# Pinout.net
KiCad netlist of a schematic drawn in Altium Designer
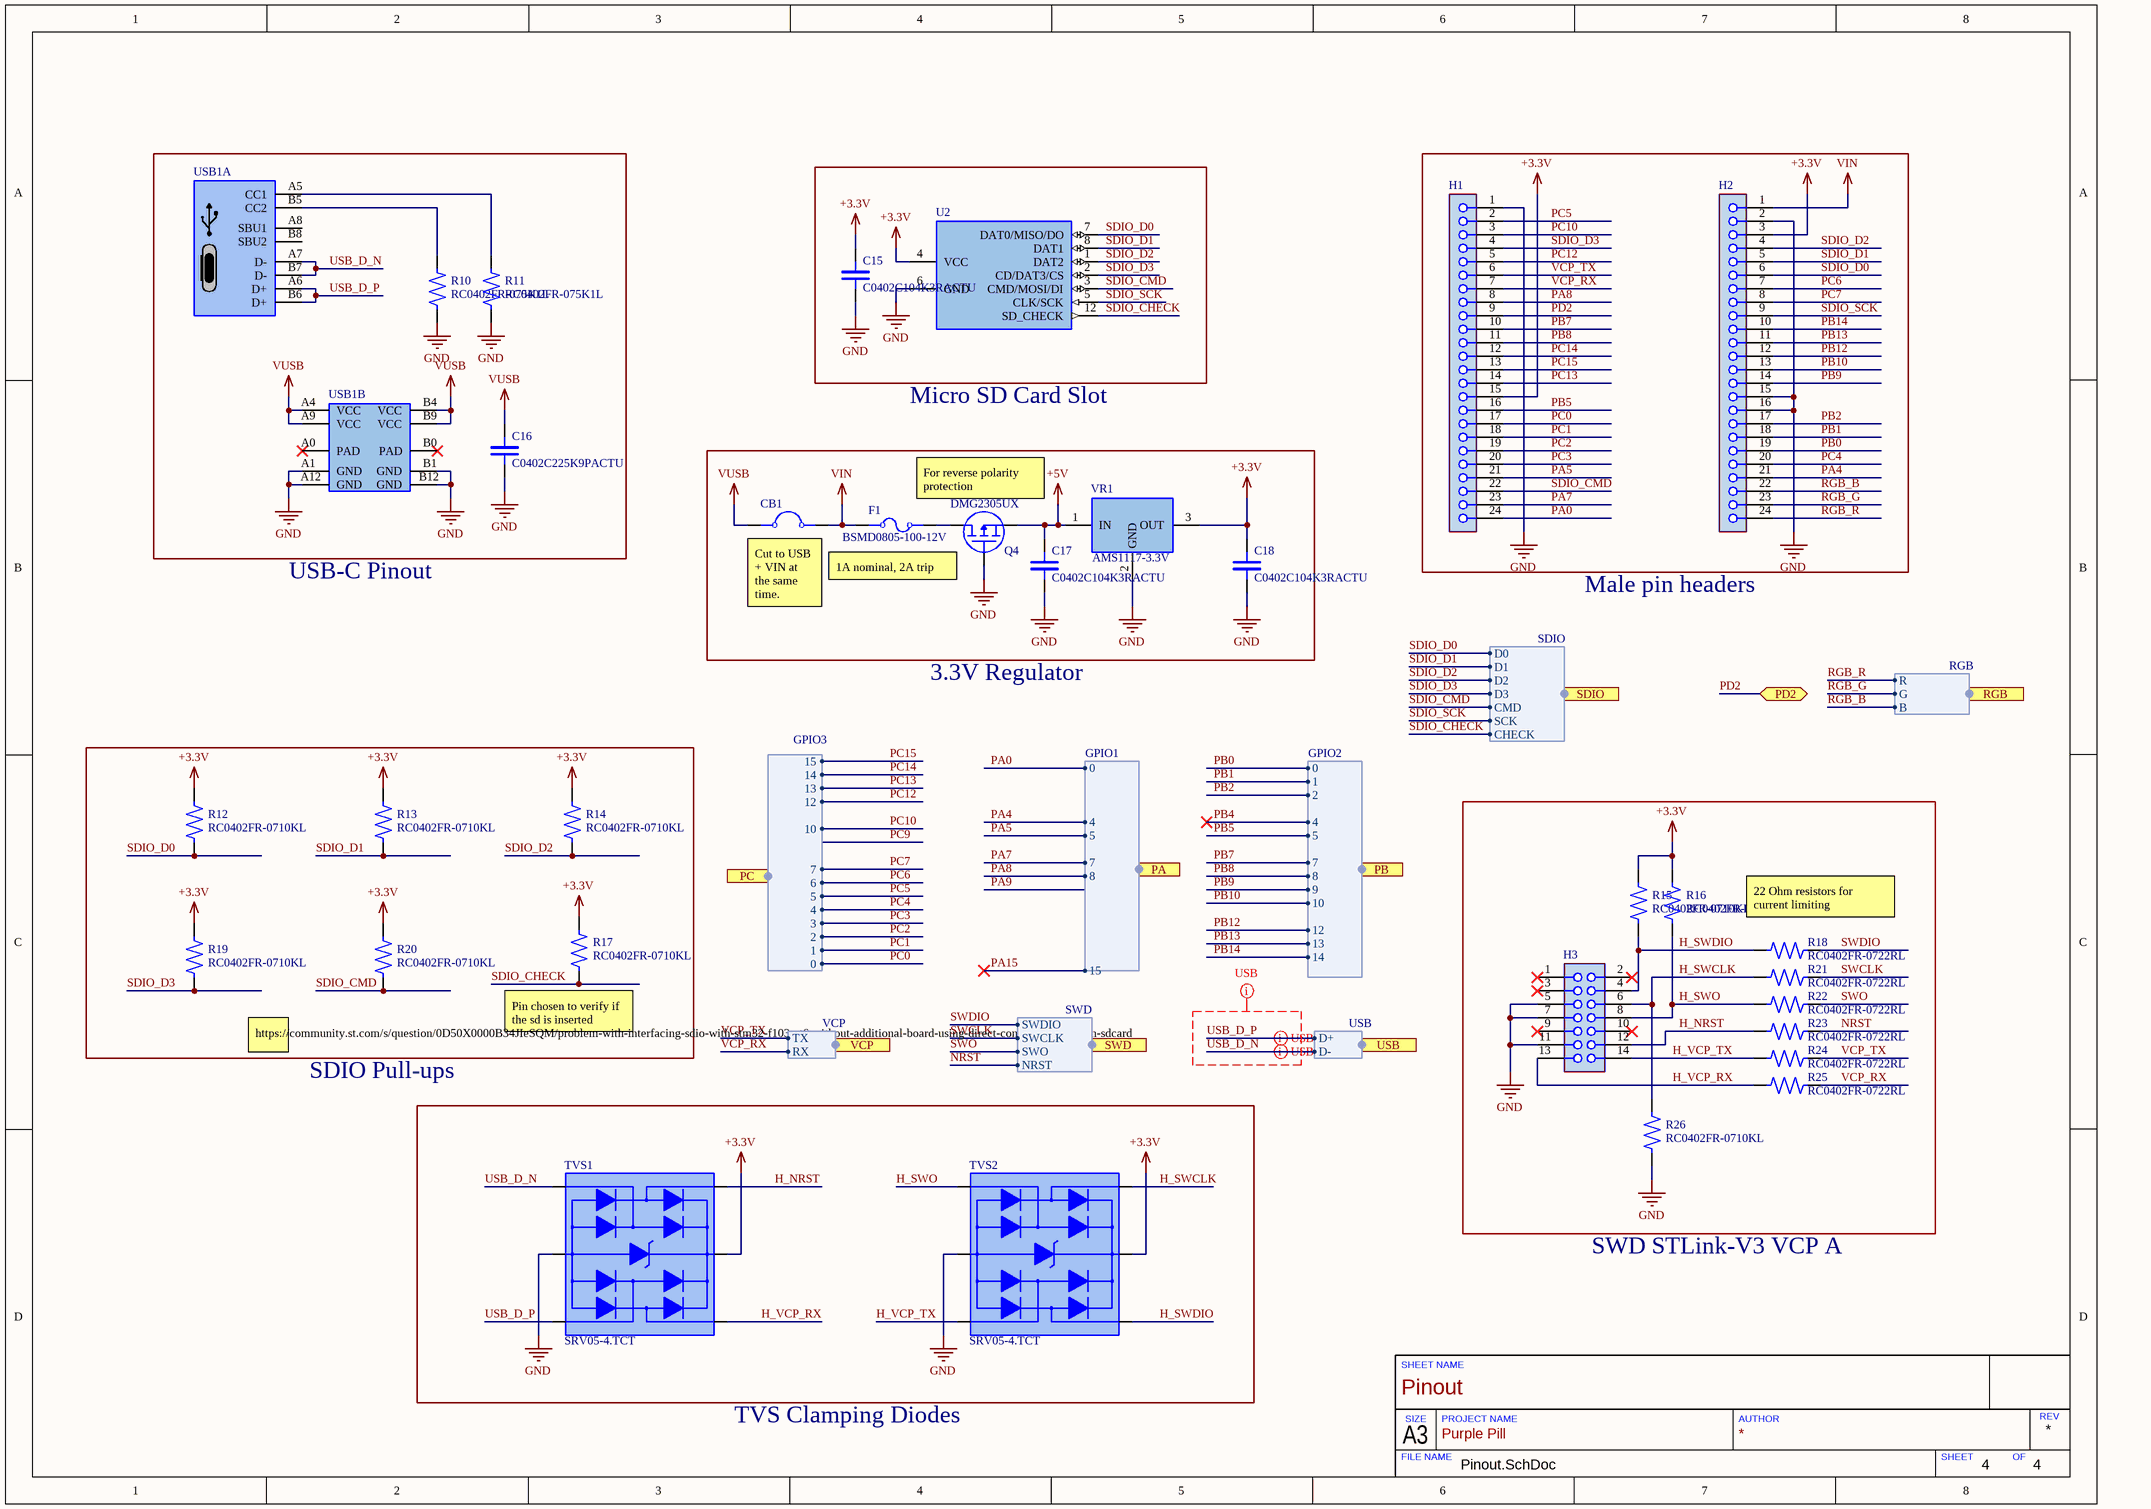
[diagram p0: Pinout.SchDoc]

(export (version "E")
  (design (tool "Eeschema 10.0.6"))
  (components
    (comp (ref "C15")
      (value "C0402C104K3RACTU")
      (footprint "CM0402_KEMET")
      (description "0.1 µF ±10% 25V Ceramic Capacitor X7R 0402 (1005 Metric")
      (fields (field (name "MANUFACTURER") "KEMET") (field (name "TOLERANCE") "10%"))
      (libsource (lib "STAR UC3M") (part "Non-polar capacitor"))
    )
    (comp (ref "C16")
      (value "C0402C225K9PACTU")
      (footprint "CM0402_KEMET")
      (description "2.2 µF ±10% 6.3V Ceramic Capacitor X5R 0402 (1005 Metric)")
      (fields (field (name "MANUFACTURER") "KEMET") (field (name "TOLERANCE") "10%"))
      (libsource (lib "STAR UC3M") (part "Non-polar capacitor"))
    )
    (comp (ref "C17")
      (value "C0402C104K3RACTU")
      (footprint "CM0402_KEMET")
      (description "0.1 µF ±10% 25V Ceramic Capacitor X7R 0402 (1005 Metric")
      (fields (field (name "MANUFACTURER") "KEMET") (field (name "TOLERANCE") "10%"))
      (libsource (lib "STAR UC3M") (part "Non-polar capacitor"))
    )
    (comp (ref "C18")
      (value "C0402C104K3RACTU")
      (footprint "CM0402_KEMET")
      (description "0.1 µF ±10% 25V Ceramic Capacitor X7R 0402 (1005 Metric")
      (fields (field (name "MANUFACTURER") "KEMET") (field (name "TOLERANCE") "10%"))
      (libsource (lib "STAR UC3M") (part "Non-polar capacitor"))
    )
    (comp (ref "CB1")
      (value "NC_JumperCircular")
      (footprint "NC_CircleJumper")
      (description "Jumper normally closed circular circuit breakers")
      (libsource (lib "STAR UC3M") (part "Closed Circuit Breaker"))
    )
    (comp (ref "F1")
      (value "BSMD0805-100-12V")
      (footprint "PTC0805")
      (description "12V 1A 40A 500mW -40℃~+85℃ 2A 40mΩ 300ms 270mΩ 0805 Resettable Fuses ROHS")
      (fields (field (name "MANUFACTURER") "BHFUSE") (field (name "LCSC PART#") "C910823"))
      (libsource (lib "STAR UC3M") (part "Resetteable fuse"))
    )
    (comp (ref "H1")
      (value "1x24MaleStraight_2.54")
      (footprint "1x24-Male-Straight-Pin_Header")
      (description "Connector Header Through Hole 24 position 1 row 0.100\" (2.54mm)")
      (fields (field (name "MANUFACTURER") "Variable"))
      (libsource (lib "STAR UC3M") (part "1x24PinHeader"))
    )
    (comp (ref "H2")
      (value "1x24MaleStraight_2.54")
      (footprint "1x24-Male-Straight-Pin_Header")
      (description "Connector Header Through Hole 24 position 1 row 0.100\" (2.54mm)")
      (fields (field (name "MANUFACTURER") "Variable"))
      (libsource (lib "STAR UC3M") (part "1x24PinHeader"))
    )
    (comp (ref "H3")
      (value "2x07MaleStraight_1.27")
      (footprint "2x07-Male-Straight-Pin_Header_1.27")
      (description "Connector Header Through Hole 14 position 2 rows 0.050\" (1.27mm)")
      (libsource (lib "STAR UC3M") (part "2x07PinHeader"))
    )
    (comp (ref "Q4")
      (value "DMG2305UX")
      (footprint "SOT23-3")
      (fields (field (name "MANUFACTURER") "Diodes Incorporated") (field (name "LCSC PART#") "C2940629"))
      (libsource (lib "STAR UC3M") (part "MOSFET enh P-channel"))
    )
    (comp (ref "R10")
      (value "RC0402FR-075K1L")
      (footprint "R0402_YAGEO")
      (description "5.1 kOhms ±1% 0.063W, 1/16W Chip Resistor 0402 (1005 Metric) Moisture Resistant Thick Film")
      (fields (field (name "MANUFACTURER") "YAGEO") (field (name "TOLERANCE") "1%"))
      (libsource (lib "STAR UC3M") (part "Resistor"))
    )
    (comp (ref "R11")
      (value "RC0402FR-075K1L")
      (footprint "R0402_YAGEO")
      (description "5.1 kOhms ±1% 0.063W, 1/16W Chip Resistor 0402 (1005 Metric) Moisture Resistant Thick Film")
      (fields (field (name "MANUFACTURER") "YAGEO") (field (name "TOLERANCE") "1%"))
      (libsource (lib "STAR UC3M") (part "Resistor"))
    )
    (comp (ref "R12")
      (value "RC0402FR-0710KL")
      (footprint "R0402_YAGEO")
      (description "10 kOhms ±1% 0.063W, 1/16W Chip Resistor 0402 (1005 Metric) Moisture Resistant Thick Film")
      (fields (field (name "TOLERANCE") "1%") (field (name "MANUFACTURER") "YAGEO"))
      (libsource (lib "STAR UC3M") (part "Resistor"))
    )
    (comp (ref "R13")
      (value "RC0402FR-0710KL")
      (footprint "R0402_YAGEO")
      (description "10 kOhms ±1% 0.063W, 1/16W Chip Resistor 0402 (1005 Metric) Moisture Resistant Thick Film")
      (fields (field (name "TOLERANCE") "1%") (field (name "MANUFACTURER") "YAGEO"))
      (libsource (lib "STAR UC3M") (part "Resistor"))
    )
    (comp (ref "R14")
      (value "RC0402FR-0710KL")
      (footprint "R0402_YAGEO")
      (description "10 kOhms ±1% 0.063W, 1/16W Chip Resistor 0402 (1005 Metric) Moisture Resistant Thick Film")
      (fields (field (name "TOLERANCE") "1%") (field (name "MANUFACTURER") "YAGEO"))
      (libsource (lib "STAR UC3M") (part "Resistor"))
    )
    (comp (ref "R15")
      (value "RC0402FR-0710KL")
      (footprint "R0402_YAGEO")
      (description "10 kOhms ±1% 0.063W, 1/16W Chip Resistor 0402 (1005 Metric) Moisture Resistant Thick Film")
      (fields (field (name "TOLERANCE") "1%") (field (name "MANUFACTURER") "YAGEO"))
      (libsource (lib "STAR UC3M") (part "Resistor"))
    )
    (comp (ref "R16")
      (value "RC0402FR-0710KL")
      (footprint "R0402_YAGEO")
      (description "10 kOhms ±1% 0.063W, 1/16W Chip Resistor 0402 (1005 Metric) Moisture Resistant Thick Film")
      (fields (field (name "TOLERANCE") "1%") (field (name "MANUFACTURER") "YAGEO"))
      (libsource (lib "STAR UC3M") (part "Resistor"))
    )
    (comp (ref "R17")
      (value "RC0402FR-0710KL")
      (footprint "R0402_YAGEO")
      (description "10 kOhms ±1% 0.063W, 1/16W Chip Resistor 0402 (1005 Metric) Moisture Resistant Thick Film")
      (fields (field (name "TOLERANCE") "1%") (field (name "MANUFACTURER") "YAGEO"))
      (libsource (lib "STAR UC3M") (part "Resistor"))
    )
    (comp (ref "R18")
      (value "RC0402FR-0722RL")
      (footprint "R0402_YAGEO")
      (description "22 Ohms ±1% 0.063W, 1/16W Chip Resistor 0402 (1005 Metric) Moisture Resistant Thick Film")
      (fields (field (name "TOLERANCE") "1%") (field (name "MANUFACTURER") "YAGEO"))
      (libsource (lib "STAR UC3M") (part "Resistor"))
    )
    (comp (ref "R19")
      (value "RC0402FR-0710KL")
      (footprint "R0402_YAGEO")
      (description "10 kOhms ±1% 0.063W, 1/16W Chip Resistor 0402 (1005 Metric) Moisture Resistant Thick Film")
      (fields (field (name "TOLERANCE") "1%") (field (name "MANUFACTURER") "YAGEO"))
      (libsource (lib "STAR UC3M") (part "Resistor"))
    )
    (comp (ref "R20")
      (value "RC0402FR-0710KL")
      (footprint "R0402_YAGEO")
      (description "10 kOhms ±1% 0.063W, 1/16W Chip Resistor 0402 (1005 Metric) Moisture Resistant Thick Film")
      (fields (field (name "TOLERANCE") "1%") (field (name "MANUFACTURER") "YAGEO"))
      (libsource (lib "STAR UC3M") (part "Resistor"))
    )
    (comp (ref "R21")
      (value "RC0402FR-0722RL")
      (footprint "R0402_YAGEO")
      (description "22 Ohms ±1% 0.063W, 1/16W Chip Resistor 0402 (1005 Metric) Moisture Resistant Thick Film")
      (fields (field (name "TOLERANCE") "1%") (field (name "MANUFACTURER") "YAGEO"))
      (libsource (lib "STAR UC3M") (part "Resistor"))
    )
    (comp (ref "R22")
      (value "RC0402FR-0722RL")
      (footprint "R0402_YAGEO")
      (description "22 Ohms ±1% 0.063W, 1/16W Chip Resistor 0402 (1005 Metric) Moisture Resistant Thick Film")
      (fields (field (name "TOLERANCE") "1%") (field (name "MANUFACTURER") "YAGEO"))
      (libsource (lib "STAR UC3M") (part "Resistor"))
    )
    (comp (ref "R23")
      (value "RC0402FR-0722RL")
      (footprint "R0402_YAGEO")
      (description "22 Ohms ±1% 0.063W, 1/16W Chip Resistor 0402 (1005 Metric) Moisture Resistant Thick Film")
      (fields (field (name "TOLERANCE") "1%") (field (name "MANUFACTURER") "YAGEO"))
      (libsource (lib "STAR UC3M") (part "Resistor"))
    )
    (comp (ref "R24")
      (value "RC0402FR-0722RL")
      (footprint "R0402_YAGEO")
      (description "22 Ohms ±1% 0.063W, 1/16W Chip Resistor 0402 (1005 Metric) Moisture Resistant Thick Film")
      (fields (field (name "TOLERANCE") "1%") (field (name "MANUFACTURER") "YAGEO"))
      (libsource (lib "STAR UC3M") (part "Resistor"))
    )
    (comp (ref "R25")
      (value "RC0402FR-0722RL")
      (footprint "R0402_YAGEO")
      (description "22 Ohms ±1% 0.063W, 1/16W Chip Resistor 0402 (1005 Metric) Moisture Resistant Thick Film")
      (fields (field (name "TOLERANCE") "1%") (field (name "MANUFACTURER") "YAGEO"))
      (libsource (lib "STAR UC3M") (part "Resistor"))
    )
    (comp (ref "R26")
      (value "RC0402FR-0710KL")
      (footprint "R0402_YAGEO")
      (description "10 kOhms ±1% 0.063W, 1/16W Chip Resistor 0402 (1005 Metric) Moisture Resistant Thick Film")
      (fields (field (name "TOLERANCE") "1%") (field (name "MANUFACTURER") "YAGEO"))
      (libsource (lib "STAR UC3M") (part "Resistor"))
    )
    (comp (ref "TVS1")
      (value "SRV05-4.TCT")
      (footprint "SOT23-6")
      (description "Trans Voltage Suppressor Diode, 300W, 5V V(RWM), Unidirectional, 1 Element, Silicon")
      (fields (field (name "MANUFACTURER") "Semtech") (field (name "LCSC PART#") "C13612"))
      (libsource (lib "STAR UC3M") (part "TVS 4 array diode"))
    )
    (comp (ref "TVS2")
      (value "SRV05-4.TCT")
      (footprint "SOT23-6")
      (description "Trans Voltage Suppressor Diode, 300W, 5V V(RWM), Unidirectional, 1 Element, Silicon")
      (fields (field (name "MANUFACTURER") "Semtech") (field (name "LCSC PART#") "C13612"))
      (libsource (lib "STAR UC3M") (part "TVS 4 array diode"))
    )
    (comp (ref "U2")
      (value "104031-0811")
      (footprint "SMD_MicroSD")
      (fields (field (name "MANUFACTURER") "Molex") (field (name "LCSC PART#") "C585350"))
      (libsource (lib "STAR UC3M") (part "MicroSD"))
    )
    (comp (ref "USB1")
      (value "USB4105-GF-A")
      (footprint "USB-C horizontal smd")
      (description "USB Connectors USB Type C,2.0, Rec,SMT, 0.95mmTH Shell Stakes,G/F,RA,Top Mnt,T&R")
      (fields (field (name "MANUFACTURER") "GCT") (field (name "LCSC PART#") "C165948"))
      (libsource (lib "STAR UC3M") (part "USB C 2.X"))
    )
    (comp (ref "VR1")
      (value "AMS1117-3.3V")
      (footprint "SOT89")
      (fields (field (name "MANUFACTURER") "MSKSEMI") (field (name "LCSC PART#") "C5120796"))
      (libsource (lib "STAR UC3M") (part "Linear Regulator Fixed Without Enable"))
    )
  )
  (nets
    (net (code "9") (name "+3.3V") (class "Default")
      (node (ref "C15") (pin "2") (pinfunction "2_2") (pintype "passive"))
      (node (ref "C18") (pin "2") (pinfunction "2_2") (pintype "passive"))
      (node (ref "H1") (pin "15") (pinfunction "15_15") (pintype "passive"))
      (node (ref "H2") (pin "3") (pinfunction "3_3") (pintype "passive"))
      (node (ref "R12") (pin "2") (pinfunction "2_2") (pintype "passive"))
      (node (ref "R13") (pin "2") (pinfunction "2_2") (pintype "passive"))
      (node (ref "R14") (pin "2") (pinfunction "2_2") (pintype "passive"))
      (node (ref "R15") (pin "2") (pinfunction "2_2") (pintype "passive"))
      (node (ref "R16") (pin "2") (pinfunction "2_2") (pintype "passive"))
      (node (ref "R17") (pin "2") (pinfunction "2_2") (pintype "passive"))
      (node (ref "R19") (pin "2") (pinfunction "2_2") (pintype "passive"))
      (node (ref "R20") (pin "2") (pinfunction "2_2") (pintype "passive"))
      (node (ref "TVS1") (pin "5") (pinfunction "Gnd_5") (pintype "passive"))
      (node (ref "TVS2") (pin "5") (pinfunction "Gnd_5") (pintype "passive"))
      (node (ref "U2") (pin "4") (pinfunction "VCC_4") (pintype "power_in"))
      (node (ref "VR1") (pin "3") (pinfunction "OUT_3") (pintype "power_in"))
    )
    (net (code "10") (name "+5V") (class "Default")
      (node (ref "C17") (pin "2") (pinfunction "2_2") (pintype "passive"))
      (node (ref "Q4") (pin "2") (pinfunction "Source_2") (pintype "passive"))
      (node (ref "VR1") (pin "1") (pinfunction "IN_1") (pintype "power_in"))
    )
    (net (code "11") (name "/H_NRST") (class "Default")
      (node (ref "H3") (pin "12") (pinfunction "12_12") (pintype "passive"))
      (node (ref "R23") (pin "2") (pinfunction "2_2") (pintype "passive"))
      (node (ref "TVS1") (pin "6") (pinfunction "TVS1_6") (pintype "passive"))
    )
    (net (code "12") (name "/H_SWCLK") (class "Default")
      (node (ref "H3") (pin "6") (pinfunction "6_6") (pintype "passive"))
      (node (ref "R21") (pin "2") (pinfunction "2_2") (pintype "passive"))
      (node (ref "R26") (pin "2") (pinfunction "2_2") (pintype "passive"))
      (node (ref "TVS2") (pin "6") (pinfunction "TVS1_6") (pintype "passive"))
    )
    (net (code "13") (name "/H_SWDIO") (class "Default")
      (node (ref "H3") (pin "4") (pinfunction "4_4") (pintype "passive"))
      (node (ref "R15") (pin "1") (pinfunction "1_1") (pintype "passive"))
      (node (ref "R18") (pin "2") (pinfunction "2_2") (pintype "passive"))
      (node (ref "TVS2") (pin "4") (pinfunction "TVS4_4") (pintype "passive"))
    )
    (net (code "14") (name "/H_SWO") (class "Default")
      (node (ref "H3") (pin "8") (pinfunction "8_8") (pintype "passive"))
      (node (ref "R16") (pin "1") (pinfunction "1_1") (pintype "passive"))
      (node (ref "R22") (pin "2") (pinfunction "2_2") (pintype "passive"))
      (node (ref "TVS2") (pin "1") (pinfunction "TVS2_1") (pintype "passive"))
    )
    (net (code "15") (name "/H_VCP_RX") (class "Default")
      (node (ref "H3") (pin "13") (pinfunction "13_13") (pintype "passive"))
      (node (ref "R25") (pin "2") (pinfunction "2_2") (pintype "passive"))
      (node (ref "TVS1") (pin "4") (pinfunction "TVS4_4") (pintype "passive"))
    )
    (net (code "16") (name "/H_VCP_TX") (class "Default")
      (node (ref "H3") (pin "14") (pinfunction "14_14") (pintype "passive"))
      (node (ref "R24") (pin "2") (pinfunction "2_2") (pintype "passive"))
      (node (ref "TVS2") (pin "3") (pinfunction "TVS3_3") (pintype "passive"))
    )
    (net (code "17") (name "/NRST") (class "Default")
      (node (ref "R23") (pin "1") (pinfunction "1_1") (pintype "passive"))
    )
    (net (code "18") (name "/PA0") (class "Default")
      (node (ref "H1") (pin "24") (pinfunction "24_24") (pintype "passive"))
    )
    (net (code "19") (name "/PA4") (class "Default")
      (node (ref "H2") (pin "21") (pinfunction "21_21") (pintype "passive"))
    )
    (net (code "20") (name "/PA5") (class "Default")
      (node (ref "H1") (pin "21") (pinfunction "21_21") (pintype "passive"))
    )
    (net (code "21") (name "/PA7") (class "Default")
      (node (ref "H1") (pin "23") (pinfunction "23_23") (pintype "passive"))
    )
    (net (code "22") (name "/PA8") (class "Default")
      (node (ref "H1") (pin "8") (pinfunction "8_8") (pintype "passive"))
    )
    (net (code "25") (name "/PB0") (class "Default")
      (node (ref "H2") (pin "19") (pinfunction "19_19") (pintype "passive"))
    )
    (net (code "26") (name "/PB1") (class "Default")
      (node (ref "H2") (pin "18") (pinfunction "18_18") (pintype "passive"))
    )
    (net (code "27") (name "/PB2") (class "Default")
      (node (ref "H2") (pin "17") (pinfunction "17_17") (pintype "passive"))
    )
    (net (code "29") (name "/PB5") (class "Default")
      (node (ref "H1") (pin "16") (pinfunction "16_16") (pintype "passive"))
    )
    (net (code "30") (name "/PB7") (class "Default")
      (node (ref "H1") (pin "10") (pinfunction "10_10") (pintype "passive"))
    )
    (net (code "31") (name "/PB8") (class "Default")
      (node (ref "H1") (pin "11") (pinfunction "11_11") (pintype "passive"))
    )
    (net (code "32") (name "/PB9") (class "Default")
      (node (ref "H2") (pin "14") (pinfunction "14_14") (pintype "passive"))
    )
    (net (code "33") (name "/PB10") (class "Default")
      (node (ref "H2") (pin "13") (pinfunction "13_13") (pintype "passive"))
    )
    (net (code "34") (name "/PB12") (class "Default")
      (node (ref "H2") (pin "12") (pinfunction "12_12") (pintype "passive"))
    )
    (net (code "35") (name "/PB13") (class "Default")
      (node (ref "H2") (pin "11") (pinfunction "11_11") (pintype "passive"))
    )
    (net (code "36") (name "/PB14") (class "Default")
      (node (ref "H2") (pin "10") (pinfunction "10_10") (pintype "passive"))
    )
    (net (code "37") (name "/PC0") (class "Default")
      (node (ref "H1") (pin "17") (pinfunction "17_17") (pintype "passive"))
    )
    (net (code "38") (name "/PC1") (class "Default")
      (node (ref "H1") (pin "18") (pinfunction "18_18") (pintype "passive"))
    )
    (net (code "39") (name "/PC2") (class "Default")
      (node (ref "H1") (pin "19") (pinfunction "19_19") (pintype "passive"))
    )
    (net (code "40") (name "/PC3") (class "Default")
      (node (ref "H1") (pin "20") (pinfunction "20_20") (pintype "passive"))
    )
    (net (code "41") (name "/PC4") (class "Default")
      (node (ref "H2") (pin "20") (pinfunction "20_20") (pintype "passive"))
    )
    (net (code "42") (name "/PC5") (class "Default")
      (node (ref "H1") (pin "2") (pinfunction "2_2") (pintype "passive"))
    )
    (net (code "43") (name "/PC6") (class "Default")
      (node (ref "H2") (pin "7") (pinfunction "7_7") (pintype "passive"))
    )
    (net (code "44") (name "/PC7") (class "Default")
      (node (ref "H2") (pin "8") (pinfunction "8_8") (pintype "passive"))
    )
    (net (code "46") (name "/PC10") (class "Default")
      (node (ref "H1") (pin "3") (pinfunction "3_3") (pintype "passive"))
    )
    (net (code "47") (name "/PC12") (class "Default")
      (node (ref "H1") (pin "5") (pinfunction "5_5") (pintype "passive"))
    )
    (net (code "48") (name "/PC13") (class "Default")
      (node (ref "H1") (pin "14") (pinfunction "14_14") (pintype "passive"))
    )
    (net (code "49") (name "/PC14") (class "Default")
      (node (ref "H1") (pin "12") (pinfunction "12_12") (pintype "passive"))
    )
    (net (code "50") (name "/PC15") (class "Default")
      (node (ref "H1") (pin "13") (pinfunction "13_13") (pintype "passive"))
    )
    (net (code "51") (name "/PD2") (class "Default")
      (node (ref "H1") (pin "9") (pinfunction "9_9") (pintype "passive"))
    )
    (net (code "52") (name "/RGB_B") (class "Default")
      (node (ref "H2") (pin "22") (pinfunction "22_22") (pintype "passive"))
    )
    (net (code "53") (name "/RGB_G") (class "Default")
      (node (ref "H2") (pin "23") (pinfunction "23_23") (pintype "passive"))
    )
    (net (code "54") (name "/RGB_R") (class "Default")
      (node (ref "H2") (pin "24") (pinfunction "24_24") (pintype "passive"))
    )
    (net (code "55") (name "/SDIO_CHECK") (class "Default")
      (node (ref "R17") (pin "1") (pinfunction "1_1") (pintype "passive"))
      (node (ref "U2") (pin "12") (pinfunction "SD_CHECK_12") (pintype "output"))
    )
    (net (code "56") (name "/SDIO_CMD") (class "Default")
      (node (ref "H1") (pin "22") (pinfunction "22_22") (pintype "passive"))
      (node (ref "R20") (pin "1") (pinfunction "1_1") (pintype "passive"))
      (node (ref "U2") (pin "3") (pinfunction "CMD/MOSI/DI_3") (pintype "bidirectional"))
    )
    (net (code "57") (name "/SDIO_D0") (class "Default")
      (node (ref "H2") (pin "6") (pinfunction "6_6") (pintype "passive"))
      (node (ref "R12") (pin "1") (pinfunction "1_1") (pintype "passive"))
      (node (ref "U2") (pin "7") (pinfunction "DAT0/MISO/DO_7") (pintype "bidirectional"))
    )
    (net (code "58") (name "/SDIO_D1") (class "Default")
      (node (ref "H2") (pin "5") (pinfunction "5_5") (pintype "passive"))
      (node (ref "R13") (pin "1") (pinfunction "1_1") (pintype "passive"))
      (node (ref "U2") (pin "8") (pinfunction "DAT1_8") (pintype "bidirectional"))
    )
    (net (code "59") (name "/SDIO_D2") (class "Default")
      (node (ref "H2") (pin "4") (pinfunction "4_4") (pintype "passive"))
      (node (ref "R14") (pin "1") (pinfunction "1_1") (pintype "passive"))
      (node (ref "U2") (pin "1") (pinfunction "DAT2_1") (pintype "bidirectional"))
    )
    (net (code "60") (name "/SDIO_D3") (class "Default")
      (node (ref "H1") (pin "4") (pinfunction "4_4") (pintype "passive"))
      (node (ref "R19") (pin "1") (pinfunction "1_1") (pintype "passive"))
      (node (ref "U2") (pin "2") (pinfunction "CD/DAT3/CS_2") (pintype "bidirectional"))
    )
    (net (code "61") (name "/SDIO_SCK") (class "Default")
      (node (ref "H2") (pin "9") (pinfunction "9_9") (pintype "passive"))
      (node (ref "U2") (pin "5") (pinfunction "CLK/SCK_5") (pintype "input"))
    )
    (net (code "62") (name "/SWCLK") (class "Default")
      (node (ref "R21") (pin "1") (pinfunction "1_1") (pintype "passive"))
    )
    (net (code "63") (name "/SWDIO") (class "Default")
      (node (ref "R18") (pin "1") (pinfunction "1_1") (pintype "passive"))
    )
    (net (code "64") (name "/SWO") (class "Default")
      (node (ref "R22") (pin "1") (pinfunction "1_1") (pintype "passive"))
    )
    (net (code "65") (name "/USB_D_N") (class "Default")
      (node (ref "TVS1") (pin "1") (pinfunction "TVS2_1") (pintype "passive"))
      (node (ref "USB1") (pin "A7") (pinfunction "D-_A7") (pintype "passive"))
      (node (ref "USB1") (pin "B7") (pinfunction "D-_B7") (pintype "passive"))
    )
    (net (code "66") (name "/USB_D_P") (class "Default")
      (node (ref "TVS1") (pin "3") (pinfunction "TVS3_3") (pintype "passive"))
      (node (ref "USB1") (pin "A6") (pinfunction "D+_A6") (pintype "passive"))
      (node (ref "USB1") (pin "B6") (pinfunction "D+_B6") (pintype "passive"))
    )
    (net (code "67") (name "/VCP_RX") (class "Default")
      (node (ref "H1") (pin "7") (pinfunction "7_7") (pintype "passive"))
      (node (ref "R25") (pin "1") (pinfunction "1_1") (pintype "passive"))
    )
    (net (code "68") (name "/VCP_TX") (class "Default")
      (node (ref "H1") (pin "6") (pinfunction "6_6") (pintype "passive"))
      (node (ref "R24") (pin "1") (pinfunction "1_1") (pintype "passive"))
    )
    (net (code "77") (name "GND") (class "Default")
      (node (ref "C15") (pin "1") (pinfunction "1_1") (pintype "passive"))
      (node (ref "C16") (pin "1") (pinfunction "1_1") (pintype "passive"))
      (node (ref "C17") (pin "1") (pinfunction "1_1") (pintype "passive"))
      (node (ref "C18") (pin "1") (pinfunction "1_1") (pintype "passive"))
      (node (ref "H1") (pin "1") (pinfunction "1_1") (pintype "passive"))
      (node (ref "H2") (pin "15") (pinfunction "15_15") (pintype "passive"))
      (node (ref "H2") (pin "16") (pinfunction "16_16") (pintype "passive"))
      (node (ref "H2") (pin "2") (pinfunction "2_2") (pintype "passive"))
      (node (ref "H3") (pin "11") (pinfunction "11_11") (pintype "passive"))
      (node (ref "H3") (pin "5") (pinfunction "5_5") (pintype "passive"))
      (node (ref "H3") (pin "7") (pinfunction "7_7") (pintype "passive"))
      (node (ref "Q4") (pin "1") (pinfunction "Gate_1") (pintype "passive"))
      (node (ref "R10") (pin "1") (pinfunction "1_1") (pintype "passive"))
      (node (ref "R11") (pin "1") (pinfunction "1_1") (pintype "passive"))
      (node (ref "R26") (pin "1") (pinfunction "1_1") (pintype "passive"))
      (node (ref "TVS1") (pin "2") (pinfunction "VCC_2") (pintype "passive"))
      (node (ref "TVS2") (pin "2") (pinfunction "VCC_2") (pintype "passive"))
      (node (ref "U2") (pin "6") (pinfunction "GND_6") (pintype "power_in"))
      (node (ref "USB1") (pin "A1") (pinfunction "GND_A1") (pintype "passive"))
      (node (ref "USB1") (pin "A12") (pinfunction "GND_A12") (pintype "passive"))
      (node (ref "USB1") (pin "B1") (pinfunction "GND_B1") (pintype "passive"))
      (node (ref "USB1") (pin "B12") (pinfunction "GND_B12") (pintype "passive"))
      (node (ref "VR1") (pin "2") (pinfunction "GND_2") (pintype "power_in"))
    )
    (net (code "78") (name "Net-(Q4-Drain)") (class "Default")
      (node (ref "F1") (pin "2") (pinfunction "2_2") (pintype "passive"))
      (node (ref "Q4") (pin "3") (pinfunction "Drain_3") (pintype "passive"))
    )
    (net (code "79") (name "Net-(USB1A-CC1)") (class "Default")
      (node (ref "R11") (pin "2") (pinfunction "2_2") (pintype "passive"))
      (node (ref "USB1") (pin "A5") (pinfunction "CC1_A5") (pintype "passive"))
    )
    (net (code "80") (name "Net-(USB1A-CC2)") (class "Default")
      (node (ref "R10") (pin "2") (pinfunction "2_2") (pintype "passive"))
      (node (ref "USB1") (pin "B5") (pinfunction "CC2_B5") (pintype "passive"))
    )
    (net (code "81") (name "VIN") (class "Default")
      (node (ref "CB1") (pin "2") (pinfunction "2_2") (pintype "passive"))
      (node (ref "F1") (pin "1") (pinfunction "1_1") (pintype "passive"))
      (node (ref "H2") (pin "1") (pinfunction "1_1") (pintype "passive"))
    )
    (net (code "82") (name "VUSB") (class "Default")
      (node (ref "C16") (pin "2") (pinfunction "2_2") (pintype "passive"))
      (node (ref "CB1") (pin "1") (pinfunction "1_1") (pintype "passive"))
      (node (ref "USB1") (pin "A4") (pinfunction "VCC_A4") (pintype "passive"))
      (node (ref "USB1") (pin "A9") (pinfunction "VCC_A9") (pintype "passive"))
      (node (ref "USB1") (pin "B4") (pinfunction "VCC_B4") (pintype "passive"))
      (node (ref "USB1") (pin "B9") (pinfunction "VCC_B9") (pintype "passive"))
    )
    (net (code "83") (name "unconnected-(H3-Pad1)") (class "Default")
      (node (ref "H3") (pin "1") (pinfunction "1_1") (pintype "passive+no_connect"))
    )
    (net (code "84") (name "unconnected-(H3-Pad2)") (class "Default")
      (node (ref "H3") (pin "2") (pinfunction "2_2") (pintype "passive+no_connect"))
    )
    (net (code "85") (name "unconnected-(H3-Pad3)") (class "Default")
      (node (ref "H3") (pin "3") (pinfunction "3_3") (pintype "passive+no_connect"))
    )
    (net (code "86") (name "unconnected-(H3-Pad9)") (class "Default")
      (node (ref "H3") (pin "9") (pinfunction "9_9") (pintype "passive+no_connect"))
    )
    (net (code "87") (name "unconnected-(H3-Pad10)") (class "Default")
      (node (ref "H3") (pin "10") (pinfunction "10_10") (pintype "passive+no_connect"))
    )
    (net (code "88") (name "unconnected-(USB1A-SBU1-PadA8)") (class "Default")
      (node (ref "USB1") (pin "A8") (pinfunction "SBU1_A8") (pintype "passive"))
    )
    (net (code "89") (name "unconnected-(USB1A-SBU2-PadB8)") (class "Default")
      (node (ref "USB1") (pin "B8") (pinfunction "SBU2_B8") (pintype "passive"))
    )
    (net (code "90") (name "unconnected-(USB1B-PAD-PadA0)") (class "Default")
      (node (ref "USB1") (pin "A0") (pinfunction "PAD_A0") (pintype "passive+no_connect"))
    )
    (net (code "91") (name "unconnected-(USB1B-PAD-PadB0)") (class "Default")
      (node (ref "USB1") (pin "B0") (pinfunction "PAD_B0") (pintype "passive+no_connect"))
    )
  )
)
